# KeypadDisplay_rev_A.net
KiCad netlist of a schematic drawn in EAGLE
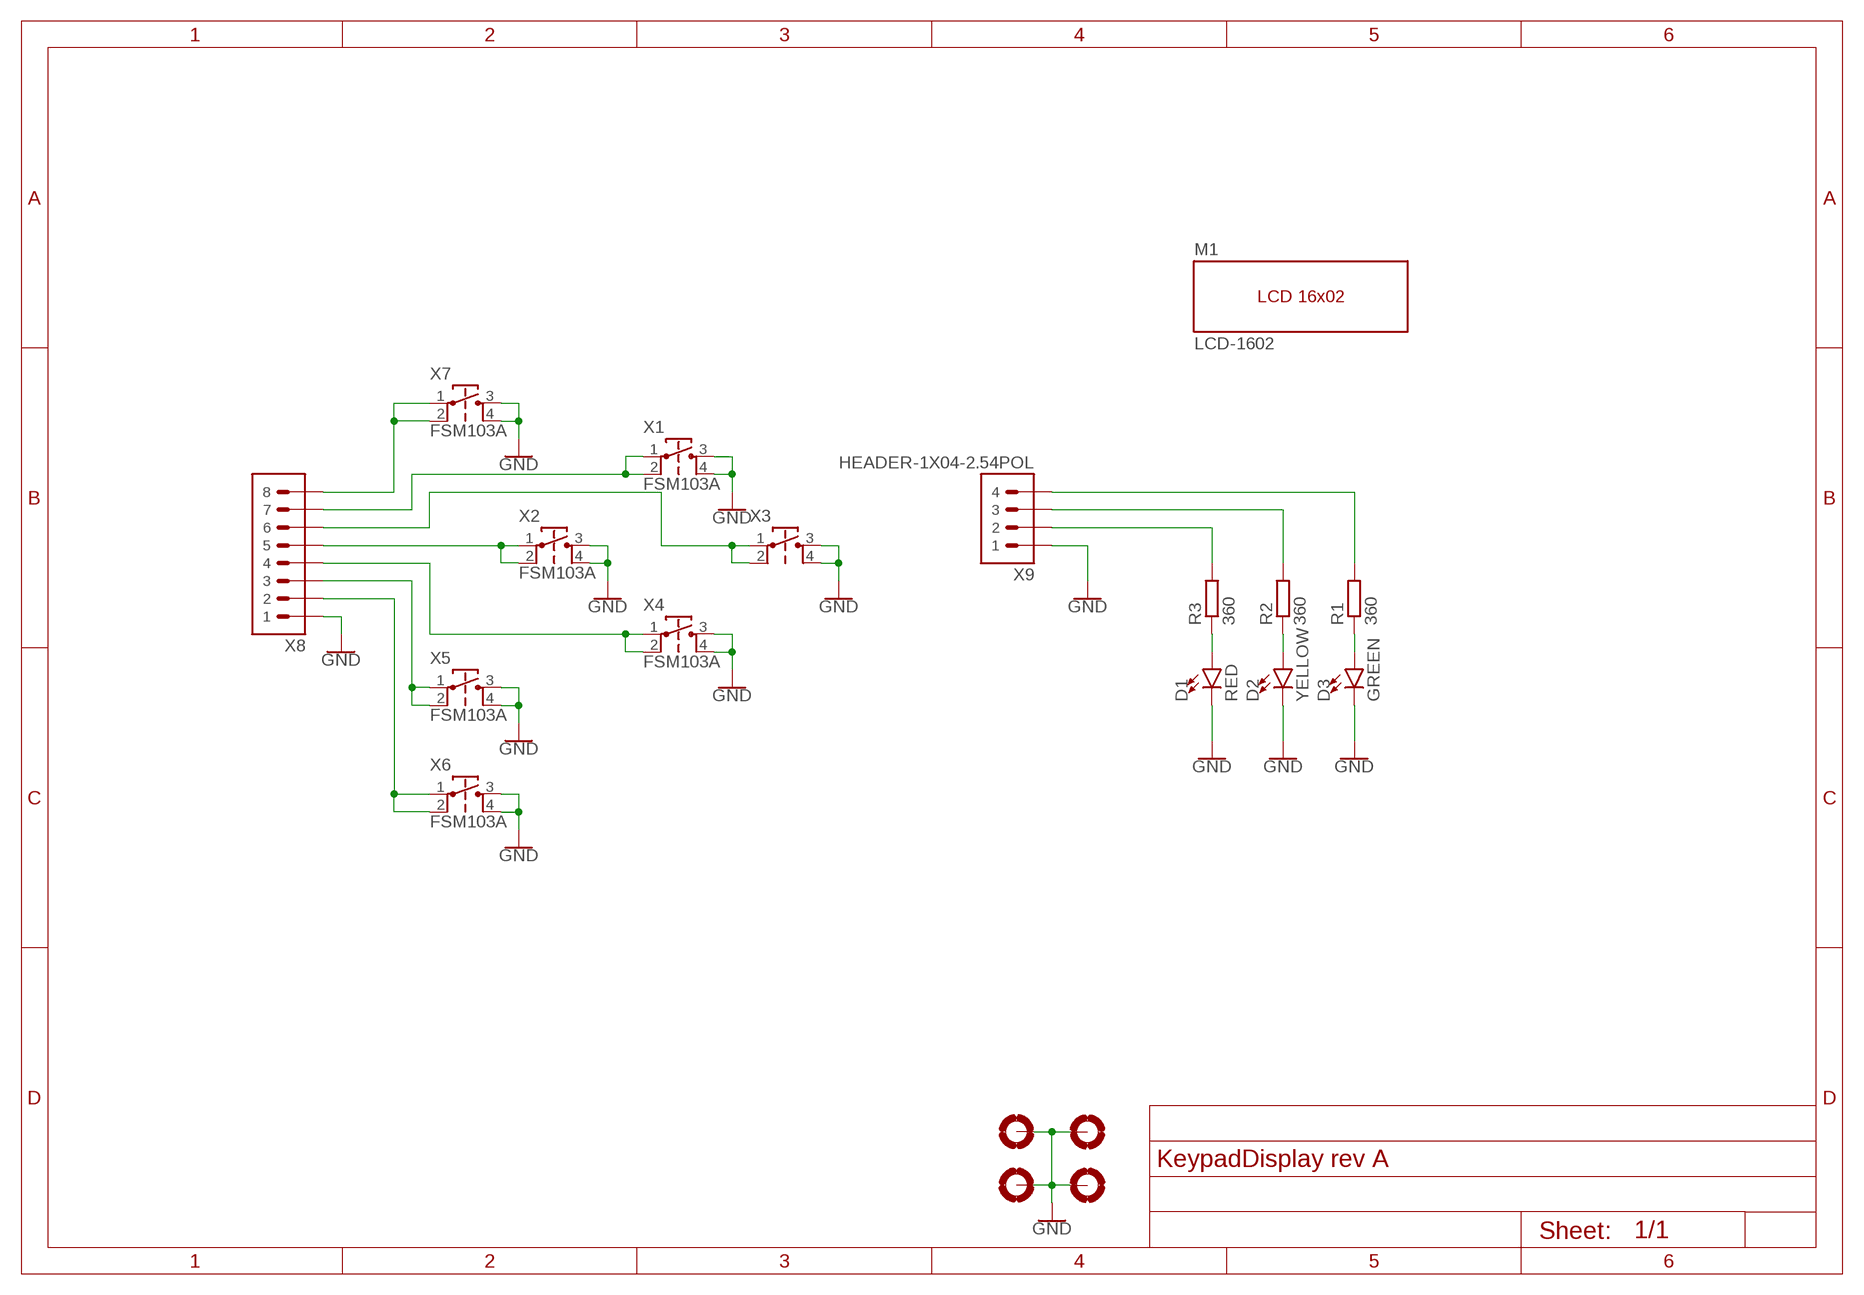
[diagram p0: schematic, sheet 1]

(export (version "E")
  (design (tool "Eeschema 10.0.6"))
  (components
    (comp (ref "D1")
      (value "RED")
      (footprint "eagle-import:LED5MM")
      (libsource (lib "eagle-import") (part "LED5MM"))
    )
    (comp (ref "D2")
      (value "YELLOW")
      (footprint "eagle-import:LED5MM")
      (libsource (lib "eagle-import") (part "LED5MM"))
    )
    (comp (ref "D3")
      (value "GREEN")
      (footprint "eagle-import:LED5MM")
      (libsource (lib "eagle-import") (part "LED5MM"))
    )
    (comp (ref "H1")
      (value "MOUNTHOLE-PAD3.0")
      (footprint "eagle-import:3.0-PAD")
      (libsource (lib "eagle-import") (part "MOUNTHOLE-PAD3.0"))
    )
    (comp (ref "H2")
      (value "MOUNTHOLE-PAD3.0")
      (footprint "eagle-import:3.0-PAD")
      (libsource (lib "eagle-import") (part "MOUNTHOLE-PAD3.0"))
    )
    (comp (ref "H3")
      (value "MOUNTHOLE-PAD3.0")
      (footprint "eagle-import:3.0-PAD")
      (libsource (lib "eagle-import") (part "MOUNTHOLE-PAD3.0"))
    )
    (comp (ref "H4")
      (value "MOUNTHOLE-PAD3.0")
      (footprint "eagle-import:3.0-PAD")
      (libsource (lib "eagle-import") (part "MOUNTHOLE-PAD3.0"))
    )
    (comp (ref "M1")
      (value "LCD-1602")
      (footprint "eagle-import:LCD-1602-NOHEADER")
      (libsource (lib "eagle-import") (part "LCD-1602-NOHEADER"))
    )
    (comp (ref "R1")
      (value "360")
      (footprint "eagle-import:0204_7")
      (libsource (lib "eagle-import") (part "R-EU_0204/7"))
    )
    (comp (ref "R2")
      (value "360")
      (footprint "eagle-import:0204_7")
      (libsource (lib "eagle-import") (part "R-EU_0204/7"))
    )
    (comp (ref "R3")
      (value "360")
      (footprint "eagle-import:0204_7")
      (libsource (lib "eagle-import") (part "R-EU_0204/7"))
    )
    (comp (ref "X1")
      (value "FSM103A")
      (footprint "eagle-import:TACT-SWITCH-FSM103A")
      (libsource (lib "eagle-import") (part "TACT-SWITCHFSM103A"))
    )
    (comp (ref "X2")
      (value "FSM103A")
      (footprint "eagle-import:TACT-SWITCH-FSM103A")
      (libsource (lib "eagle-import") (part "TACT-SWITCHFSM103A"))
    )
    (comp (ref "X3")
      (value "TACT-SWITCHFSM103A")
      (footprint "eagle-import:TACT-SWITCH-FSM103A")
      (libsource (lib "eagle-import") (part "TACT-SWITCHFSM103A"))
    )
    (comp (ref "X4")
      (value "FSM103A")
      (footprint "eagle-import:TACT-SWITCH-FSM103A")
      (libsource (lib "eagle-import") (part "TACT-SWITCHFSM103A"))
    )
    (comp (ref "X5")
      (value "FSM103A")
      (footprint "eagle-import:TACT-SWITCH-FSM103A")
      (libsource (lib "eagle-import") (part "TACT-SWITCHFSM103A"))
    )
    (comp (ref "X6")
      (value "FSM103A")
      (footprint "eagle-import:TACT-SWITCH-FSM103A")
      (libsource (lib "eagle-import") (part "TACT-SWITCHFSM103A"))
    )
    (comp (ref "X7")
      (value "FSM103A")
      (footprint "eagle-import:TACT-SWITCH-FSM103A")
      (libsource (lib "eagle-import") (part "TACT-SWITCHFSM103A"))
    )
    (comp (ref "X8")
      (value "HEADER-1X08-2.54POL")
      (footprint "eagle-import:1X08P-2.54")
      (libsource (lib "eagle-import") (part "HEADER-1X08-2.54POL"))
    )
    (comp (ref "X9")
      (value "HEADER-1X04-2.54POL")
      (footprint "eagle-import:1X04P-2.54")
      (libsource (lib "eagle-import") (part "HEADER-1X04-2.54POL"))
    )
  )
  (nets
    (net (code "1") (name "GND") (class "Default")
      (node (ref "D1") (pin "K") (pinfunction "C_K") (pintype "passive"))
      (node (ref "D2") (pin "K") (pinfunction "C_K") (pintype "passive"))
      (node (ref "D3") (pin "K") (pinfunction "C_K") (pintype "passive"))
      (node (ref "H1") (pin "B3,2") (pinfunction "MOUNT_B3,2") (pintype "passive"))
      (node (ref "H2") (pin "B3,2") (pinfunction "MOUNT_B3,2") (pintype "passive"))
      (node (ref "H3") (pin "B3,2") (pinfunction "MOUNT_B3,2") (pintype "passive"))
      (node (ref "H4") (pin "B3,2") (pinfunction "MOUNT_B3,2") (pintype "passive"))
      (node (ref "X1") (pin "3") (pinfunction "B_3") (pintype "bidirectional"))
      (node (ref "X1") (pin "4") (pinfunction "B'_4") (pintype "bidirectional"))
      (node (ref "X2") (pin "3") (pinfunction "B_3") (pintype "bidirectional"))
      (node (ref "X2") (pin "4") (pinfunction "B'_4") (pintype "bidirectional"))
      (node (ref "X3") (pin "3") (pinfunction "B_3") (pintype "bidirectional"))
      (node (ref "X3") (pin "4") (pinfunction "B'_4") (pintype "bidirectional"))
      (node (ref "X4") (pin "3") (pinfunction "B_3") (pintype "bidirectional"))
      (node (ref "X4") (pin "4") (pinfunction "B'_4") (pintype "bidirectional"))
      (node (ref "X5") (pin "3") (pinfunction "B_3") (pintype "bidirectional"))
      (node (ref "X5") (pin "4") (pinfunction "B'_4") (pintype "bidirectional"))
      (node (ref "X6") (pin "3") (pinfunction "B_3") (pintype "bidirectional"))
      (node (ref "X6") (pin "4") (pinfunction "B'_4") (pintype "bidirectional"))
      (node (ref "X7") (pin "3") (pinfunction "B_3") (pintype "bidirectional"))
      (node (ref "X7") (pin "4") (pinfunction "B'_4") (pintype "bidirectional"))
      (node (ref "X8") (pin "1") (pinfunction "1_1") (pintype "passive"))
      (node (ref "X9") (pin "1") (pinfunction "1_1") (pintype "passive"))
    )
    (net (code "2") (name "Net-(D1-PadA)") (class "Default")
      (node (ref "D1") (pin "A") (pinfunction "A_A") (pintype "passive"))
      (node (ref "R3") (pin "1") (pinfunction "1_1") (pintype "passive"))
    )
    (net (code "3") (name "Net-(D2-PadA)") (class "Default")
      (node (ref "D2") (pin "A") (pinfunction "A_A") (pintype "passive"))
      (node (ref "R2") (pin "1") (pinfunction "1_1") (pintype "passive"))
    )
    (net (code "4") (name "Net-(D3-PadA)") (class "Default")
      (node (ref "D3") (pin "A") (pinfunction "A_A") (pintype "passive"))
      (node (ref "R1") (pin "1") (pinfunction "1_1") (pintype "passive"))
    )
    (net (code "5") (name "Net-(R1-Pad2)") (class "Default")
      (node (ref "R1") (pin "2") (pinfunction "2_2") (pintype "passive"))
      (node (ref "X9") (pin "4") (pinfunction "4_4") (pintype "passive"))
    )
    (net (code "6") (name "Net-(R2-Pad2)") (class "Default")
      (node (ref "R2") (pin "2") (pinfunction "2_2") (pintype "passive"))
      (node (ref "X9") (pin "3") (pinfunction "3_3") (pintype "passive"))
    )
    (net (code "7") (name "Net-(R3-Pad2)") (class "Default")
      (node (ref "R3") (pin "2") (pinfunction "2_2") (pintype "passive"))
      (node (ref "X9") (pin "2") (pinfunction "2_2") (pintype "passive"))
    )
    (net (code "8") (name "Net-(X1-A')") (class "Default")
      (node (ref "X1") (pin "1") (pinfunction "A_1") (pintype "bidirectional"))
      (node (ref "X1") (pin "2") (pinfunction "A'_2") (pintype "bidirectional"))
      (node (ref "X8") (pin "7") (pinfunction "7_7") (pintype "passive"))
    )
    (net (code "9") (name "Net-(X2-A')") (class "Default")
      (node (ref "X2") (pin "1") (pinfunction "A_1") (pintype "bidirectional"))
      (node (ref "X2") (pin "2") (pinfunction "A'_2") (pintype "bidirectional"))
      (node (ref "X8") (pin "5") (pinfunction "5_5") (pintype "passive"))
    )
    (net (code "10") (name "Net-(X3-A')") (class "Default")
      (node (ref "X3") (pin "1") (pinfunction "A_1") (pintype "bidirectional"))
      (node (ref "X3") (pin "2") (pinfunction "A'_2") (pintype "bidirectional"))
      (node (ref "X8") (pin "6") (pinfunction "6_6") (pintype "passive"))
    )
    (net (code "11") (name "Net-(X4-A')") (class "Default")
      (node (ref "X4") (pin "1") (pinfunction "A_1") (pintype "bidirectional"))
      (node (ref "X4") (pin "2") (pinfunction "A'_2") (pintype "bidirectional"))
      (node (ref "X8") (pin "4") (pinfunction "4_4") (pintype "passive"))
    )
    (net (code "12") (name "Net-(X5-A')") (class "Default")
      (node (ref "X5") (pin "1") (pinfunction "A_1") (pintype "bidirectional"))
      (node (ref "X5") (pin "2") (pinfunction "A'_2") (pintype "bidirectional"))
      (node (ref "X8") (pin "3") (pinfunction "3_3") (pintype "passive"))
    )
    (net (code "13") (name "Net-(X6-A')") (class "Default")
      (node (ref "X6") (pin "1") (pinfunction "A_1") (pintype "bidirectional"))
      (node (ref "X6") (pin "2") (pinfunction "A'_2") (pintype "bidirectional"))
      (node (ref "X8") (pin "2") (pinfunction "2_2") (pintype "passive"))
    )
    (net (code "14") (name "Net-(X7-A')") (class "Default")
      (node (ref "X7") (pin "1") (pinfunction "A_1") (pintype "bidirectional"))
      (node (ref "X7") (pin "2") (pinfunction "A'_2") (pintype "bidirectional"))
      (node (ref "X8") (pin "8") (pinfunction "8_8") (pintype "bidirectional"))
    )
  )
)
